# Pre-Charge_Detector.net
KiCad netlist of a schematic drawn in Altium Designer
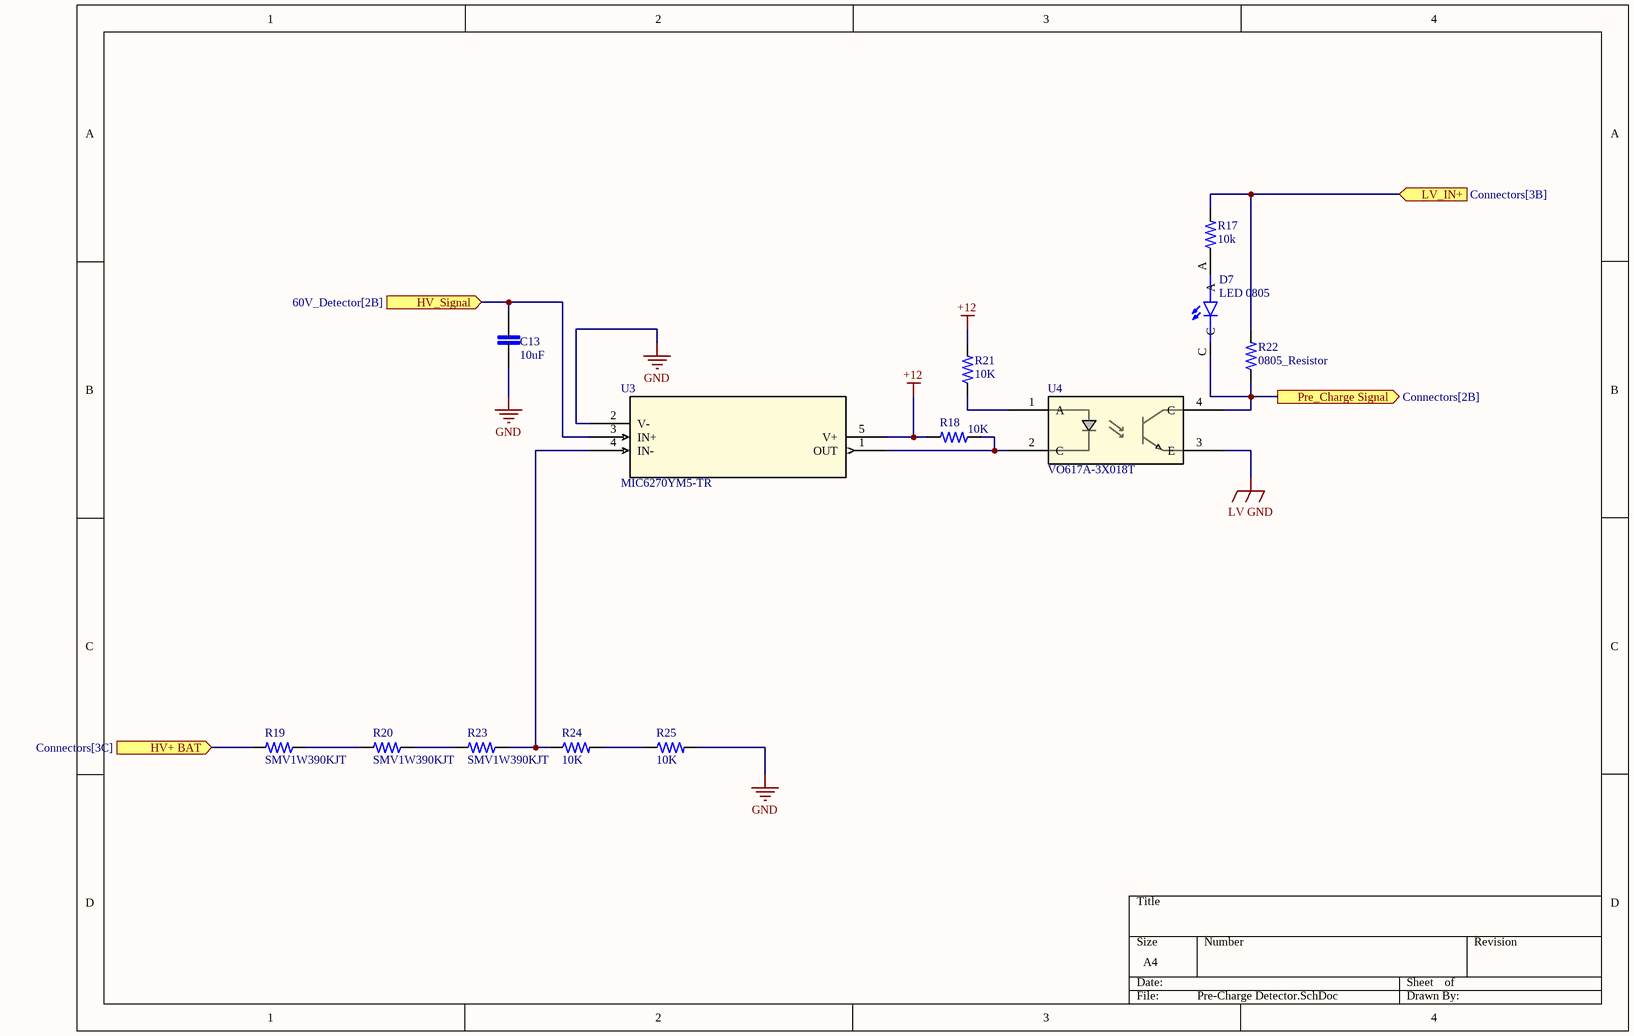
[diagram p0: Pre-Charge Detector.SchDoc]

(export (version "E")
  (design (tool "Eeschema 10.0.6"))
  (components
    (comp (ref "C13")
      (value "10uF")
      (footprint "0805")
      (fields (field (name "MP") "LD051A121KAB2A") (field (name "MF") "AVX"))
      (libsource (lib "Capacitors SMD") (part "0805_Capacitor"))
    )
    (comp (ref "D7")
      (value "LED 0805")
      (footprint "LED 0805")
      (description "LED Uni-Color Green 4-Pin Chip 0805 T/R")
      (fields (field (name "MP") "597-3305-607F"))
      (libsource (lib "LEDs SMD") (part "LED 0805"))
    )
    (comp (ref "R17")
      (value "10k")
      (footprint "0805")
      (fields
        (field (name "MP") "2-2176053-0")
        (field (name "TOLERANCE") "1%")
        (field (name "MF") "TE Connectivity")
      )
      (libsource (lib "SMD_Generic") (part "0805_Resistor"))
    )
    (comp (ref "R18")
      (value "10K")
      (footprint "0805")
      (fields
        (field (name "MP") "2-2176053-0")
        (field (name "TOLERANCE") "1%")
        (field (name "MF") "TE Connectivity")
      )
      (libsource (lib "Resistors SMD") (part "0805_Resistor"))
    )
    (comp (ref "R19")
      (value "SMV1W390KJT")
      (footprint "SMV1W390KJT")
      (fields
        (field (name "MP") "2-2176053-0")
        (field (name "TOLERANCE") "1%")
        (field (name "MF") "TE Connectivity")
      )
      (libsource (lib "Resistors SMD") (part "SMV1W390KJT"))
    )
    (comp (ref "R20")
      (value "SMV1W390KJT")
      (footprint "SMV1W390KJT")
      (fields
        (field (name "MP") "2-2176053-0")
        (field (name "TOLERANCE") "1%")
        (field (name "MF") "TE Connectivity")
      )
      (libsource (lib "Resistors SMD") (part "SMV1W390KJT"))
    )
    (comp (ref "R21")
      (value "10K")
      (footprint "0805")
      (fields
        (field (name "MP") "2-2176053-0")
        (field (name "TOLERANCE") "1%")
        (field (name "MF") "TE Connectivity")
      )
      (libsource (lib "Resistors SMD") (part "0805_Resistor"))
    )
    (comp (ref "R22")
      (value "0805_Resistor")
      (footprint "0805")
      (fields
        (field (name "MP") "2-2176053-0")
        (field (name "TOLERANCE") "1%")
        (field (name "MF") "TE Connectivity")
      )
      (libsource (lib "Resistors SMD") (part "0805_Resistor"))
    )
    (comp (ref "R23")
      (value "SMV1W390KJT")
      (footprint "SMV1W390KJT")
      (fields
        (field (name "MP") "2-2176053-0")
        (field (name "TOLERANCE") "1%")
        (field (name "MF") "TE Connectivity")
      )
      (libsource (lib "Resistors SMD") (part "SMV1W390KJT"))
    )
    (comp (ref "R24")
      (value "10K")
      (footprint "0805")
      (fields
        (field (name "MP") "2-2176053-0")
        (field (name "TOLERANCE") "1%")
        (field (name "MF") "TE Connectivity")
      )
      (libsource (lib "Resistors SMD") (part "0805_Resistor"))
    )
    (comp (ref "R25")
      (value "10K")
      (footprint "0805")
      (fields
        (field (name "MP") "2-2176053-0")
        (field (name "TOLERANCE") "1%")
        (field (name "MF") "TE Connectivity")
      )
      (libsource (lib "Resistors SMD") (part "0805_Resistor"))
    )
    (comp (ref "U3")
      (value "MIC6270YM5-TR")
      (footprint "MIC6270")
      (description "No Description Available")
      (fields (field (name "COPYRIGHT") "Copyright (C) 2024 Ultra Librarian. All rights reserved."))
      (libsource (lib "Comparators Chip SMD") (part "MIC6270YM5-TR"))
    )
    (comp (ref "U4")
      (value "VO617A-3X018T")
      (footprint "VO617A")
      (description "VO617A-3X018T Optocoupler Dc-in 1-CH Transistor Dc-out 4-PIN PDIP SMD T/r")
      (libsource (lib "Optocoupler SMD") (part "VO617A"))
    )
  )
  (nets
    (net (code "1") (name "+12") (class "Default")
      (node (ref "R18") (pin "2") (pinfunction "2_2") (pintype "passive"))
      (node (ref "R21") (pin "2") (pinfunction "2_2") (pintype "passive"))
      (node (ref "U3") (pin "5") (pinfunction "V+_5") (pintype "power_in"))
    )
    (net (code "2") (name "/HV+ BAT") (class "Default")
      (node (ref "R19") (pin "2") (pinfunction "2_2") (pintype "passive"))
    )
    (net (code "3") (name "/HV_Signal") (class "Default")
      (node (ref "C13") (pin "2") (pinfunction "2_2") (pintype "passive"))
      (node (ref "U3") (pin "3") (pinfunction "IN+_3") (pintype "input"))
    )
    (net (code "4") (name "/LV_IN+") (class "Default")
      (node (ref "R17") (pin "2") (pinfunction "2_2") (pintype "passive"))
      (node (ref "R22") (pin "2") (pinfunction "2_2") (pintype "passive"))
    )
    (net (code "5") (name "/Pre_Charge Signal") (class "Default")
      (node (ref "D7") (pin "C") (pinfunction "C_C") (pintype "passive"))
      (node (ref "R22") (pin "1") (pinfunction "1_1") (pintype "passive"))
      (node (ref "U4") (pin "4") (pinfunction "C_4") (pintype "passive"))
    )
    (net (code "6") (name "GND") (class "Default")
      (node (ref "C13") (pin "1") (pinfunction "1_1") (pintype "passive"))
      (node (ref "R25") (pin "2") (pinfunction "2_2") (pintype "passive"))
      (node (ref "U3") (pin "2") (pinfunction "V-_2") (pintype "power_in"))
    )
    (net (code "7") (name "LV GND") (class "Default")
      (node (ref "U4") (pin "3") (pinfunction "E_3") (pintype "passive"))
    )
    (net (code "8") (name "Net-(D7-PadA)") (class "Default")
      (node (ref "D7") (pin "A") (pinfunction "A_A") (pintype "passive"))
      (node (ref "R17") (pin "1") (pinfunction "1_1") (pintype "passive"))
    )
    (net (code "9") (name "Net-(R19-Pad1)") (class "Default")
      (node (ref "R19") (pin "1") (pinfunction "1_1") (pintype "passive"))
      (node (ref "R20") (pin "2") (pinfunction "2_2") (pintype "passive"))
    )
    (net (code "10") (name "Net-(R20-Pad1)") (class "Default")
      (node (ref "R20") (pin "1") (pinfunction "1_1") (pintype "passive"))
      (node (ref "R23") (pin "2") (pinfunction "2_2") (pintype "passive"))
    )
    (net (code "11") (name "Net-(R24-Pad2)") (class "Default")
      (node (ref "R24") (pin "2") (pinfunction "2_2") (pintype "passive"))
      (node (ref "R25") (pin "1") (pinfunction "1_1") (pintype "passive"))
    )
    (net (code "12") (name "Net-(U3-IN-)") (class "Default")
      (node (ref "R23") (pin "1") (pinfunction "1_1") (pintype "passive"))
      (node (ref "R24") (pin "1") (pinfunction "1_1") (pintype "passive"))
      (node (ref "U3") (pin "4") (pinfunction "IN-_4") (pintype "input"))
    )
    (net (code "13") (name "Net-(U3-OUT)") (class "Default")
      (node (ref "R18") (pin "1") (pinfunction "1_1") (pintype "passive"))
      (node (ref "U3") (pin "1") (pinfunction "OUT_1") (pintype "output"))
      (node (ref "U4") (pin "2") (pinfunction "C_2") (pintype "passive"))
    )
    (net (code "14") (name "Net-(U4-A)") (class "Default")
      (node (ref "R21") (pin "1") (pinfunction "1_1") (pintype "passive"))
      (node (ref "U4") (pin "1") (pinfunction "A_1") (pintype "passive"))
    )
  )
)
